# IRsens.net
KiCad netlist of a schematic drawn in EAGLE
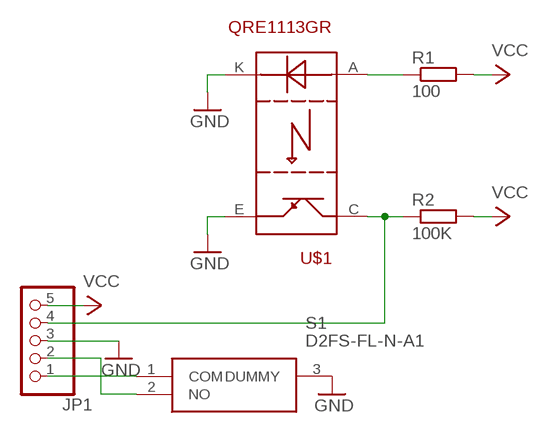
[diagram p0: schematic, sheet 1]

(export (version "E")
  (design (tool "Eeschema 10.0.6"))
  (components
    (comp (ref "JP1")
      (value "PINHD-1X5")
      (footprint "eagle-import:1X05")
      (libsource (lib "eagle-import") (part "PINHD-1X5"))
    )
    (comp (ref "R1")
      (value "100")
      (footprint "eagle-import:R0805")
      (libsource (lib "eagle-import") (part "R-EU_R0805"))
    )
    (comp (ref "R2")
      (value "100K")
      (footprint "eagle-import:R0805")
      (libsource (lib "eagle-import") (part "R-EU_R0805"))
    )
    (comp (ref "S1")
      (value "D2FS-FL-N-A1")
      (footprint "eagle-import:D2FS-FL-N-A1")
      (fields (field (name "RS_PART_NUMBER") "8046183"))
      (libsource (lib "eagle-import") (part "D2FS-FL-N-A1"))
    )
    (comp (ref "U$1")
      (value "QRE1113GR")
      (footprint "eagle-import:4LEADSMD")
      (fields (field (name "MF") "ON Semiconductor"))
      (libsource (lib "eagle-import") (part "QRE1113GR"))
    )
  )
  (nets
    (net (code "1") (name "GND") (class "Default")
      (node (ref "JP1") (pin "3") (pinfunction "3_3") (pintype "passive"))
      (node (ref "S1") (pin "3") (pinfunction "DUMMY_3") (pintype "bidirectional"))
      (node (ref "U$1") (pin "E") (pinfunction "E_E") (pintype "bidirectional"))
      (node (ref "U$1") (pin "K") (pinfunction "K_K") (pintype "bidirectional"))
    )
    (net (code "2") (name "Net-(JP1-Pad4)") (class "Default")
      (node (ref "JP1") (pin "4") (pinfunction "4_4") (pintype "passive"))
      (node (ref "R2") (pin "1") (pinfunction "1_1") (pintype "passive"))
      (node (ref "U$1") (pin "C") (pinfunction "C_C") (pintype "bidirectional"))
    )
    (net (code "3") (name "Net-(R1-Pad1)") (class "Default")
      (node (ref "R1") (pin "1") (pinfunction "1_1") (pintype "passive"))
      (node (ref "U$1") (pin "A") (pinfunction "A_A") (pintype "bidirectional"))
    )
    (net (code "4") (name "Net-(S1-COM)") (class "Default")
      (node (ref "JP1") (pin "1") (pinfunction "1_1") (pintype "passive"))
      (node (ref "S1") (pin "1") (pinfunction "COM_1") (pintype "bidirectional"))
    )
    (net (code "5") (name "Net-(S1-NO)") (class "Default")
      (node (ref "JP1") (pin "2") (pinfunction "2_2") (pintype "passive"))
      (node (ref "S1") (pin "2") (pinfunction "NO_2") (pintype "bidirectional"))
    )
    (net (code "6") (name "VCC") (class "Default")
      (node (ref "JP1") (pin "5") (pinfunction "5_5") (pintype "passive"))
      (node (ref "R1") (pin "2") (pinfunction "2_2") (pintype "passive"))
      (node (ref "R2") (pin "2") (pinfunction "2_2") (pintype "passive"))
    )
  )
)
